# 13_RK3588_PCIE2_0_PCIE3_0.net
KiCad netlist of a schematic drawn in Altium Designer
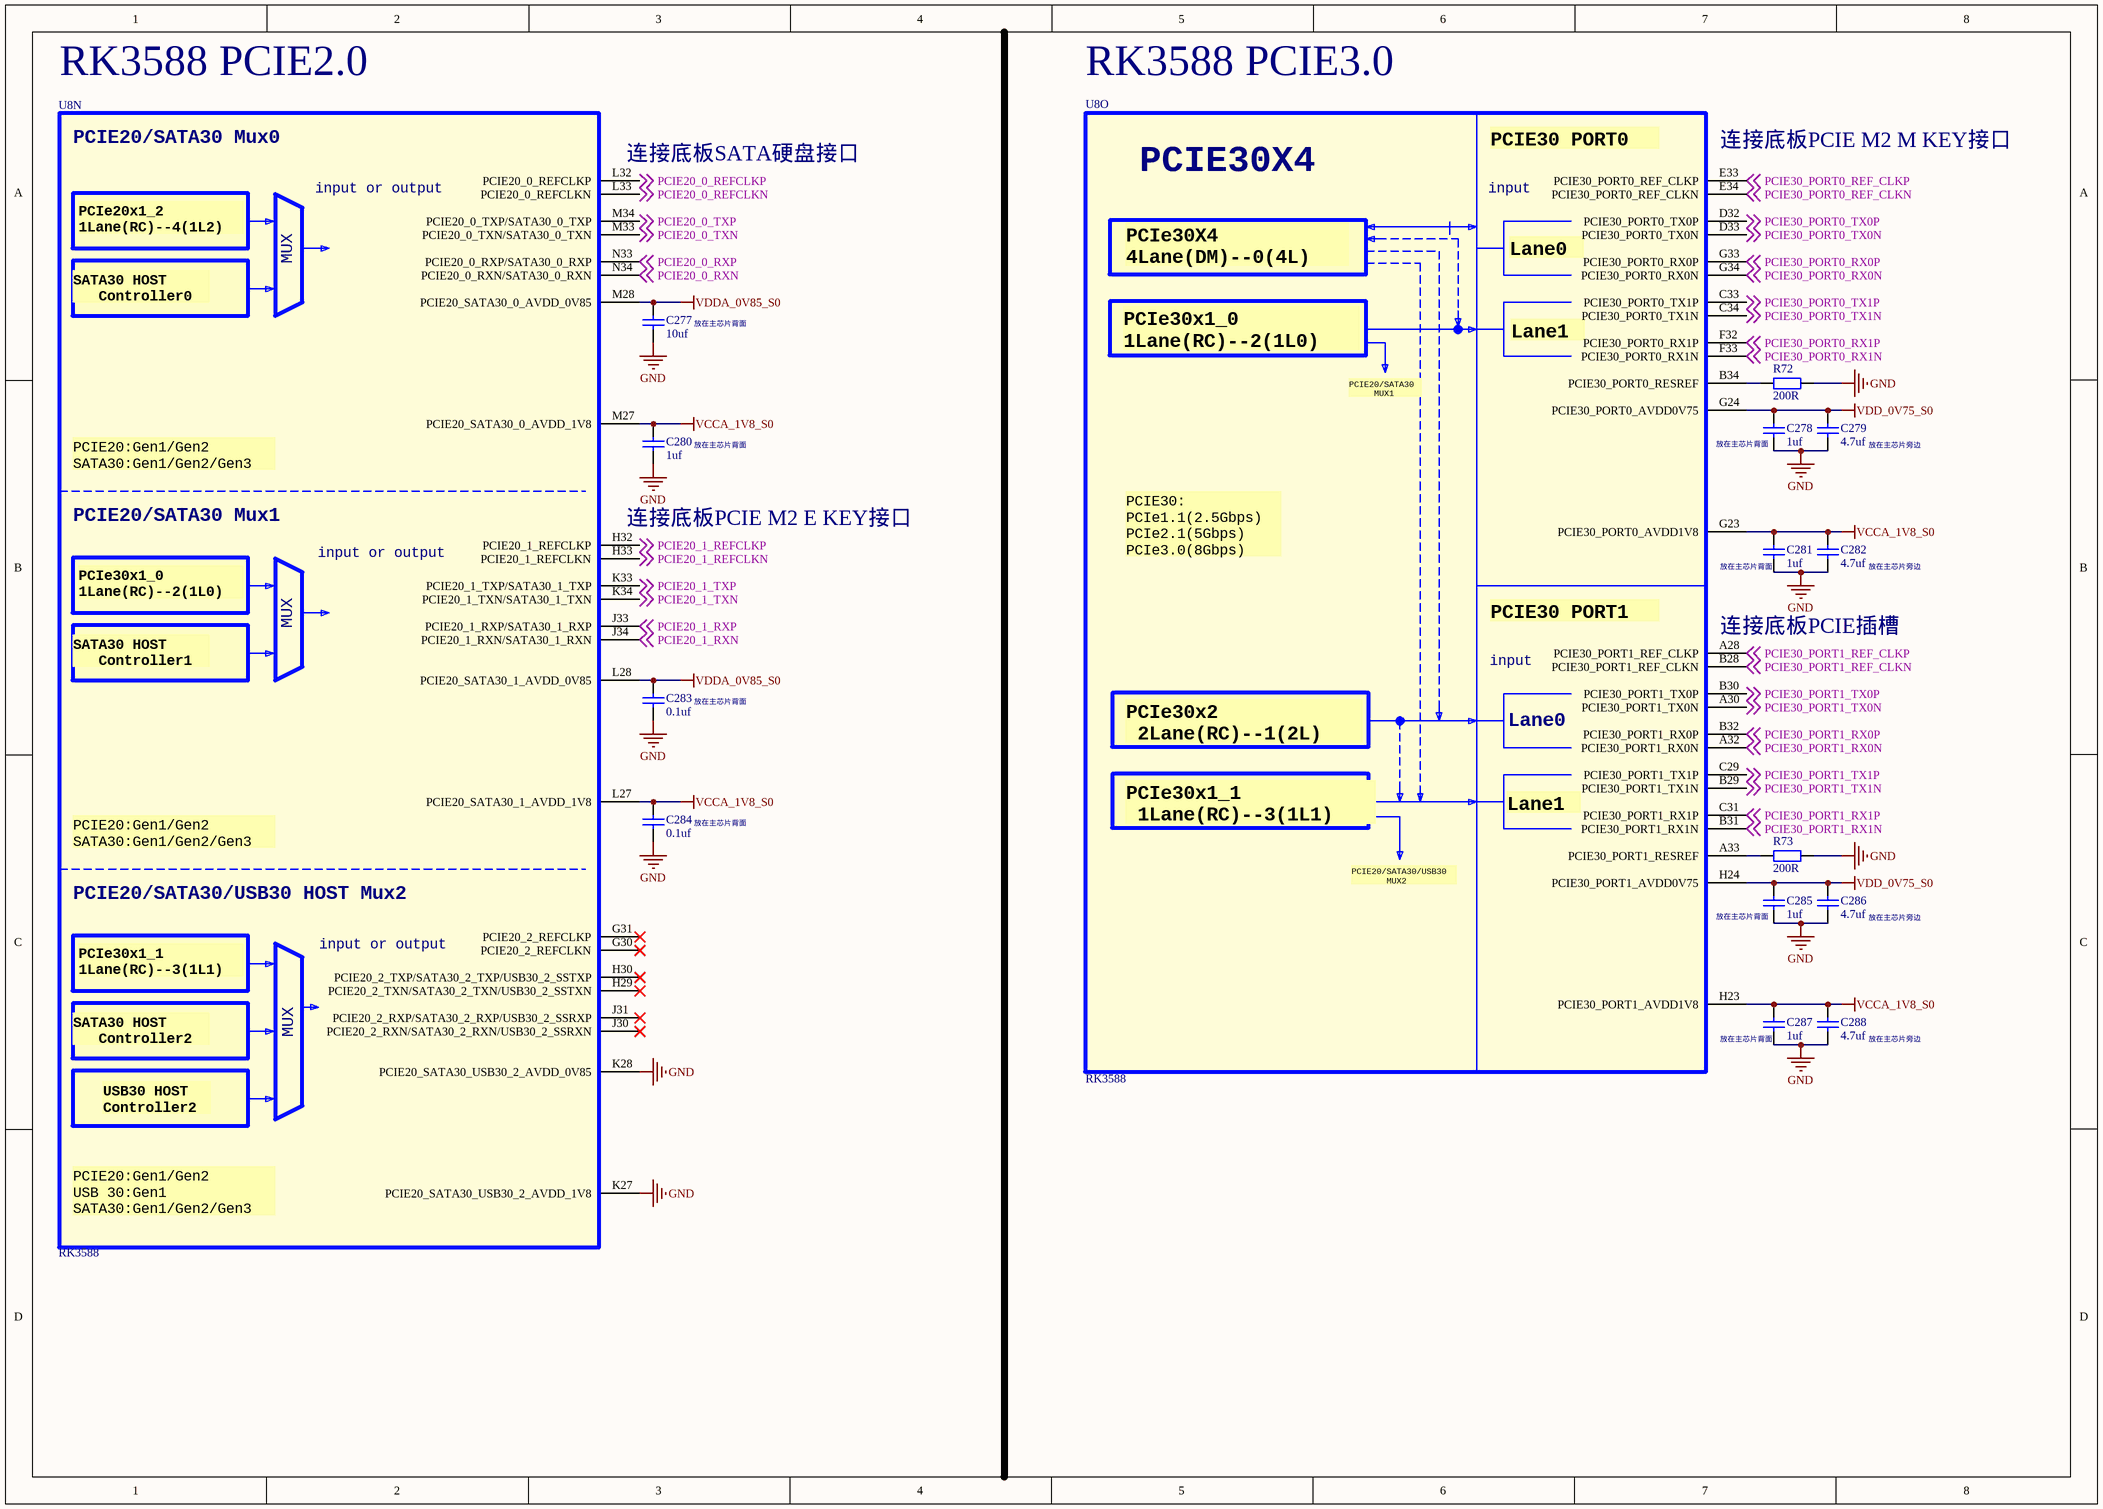
[diagram p0: 13.RK3588_PCIE2.0_PCIE3.0.SchDoc]

(export (version "E")
  (design (tool "Eeschema 10.0.6"))
  (components
    (comp (ref "C277")
      (value "10uf")
      (footprint "0.PCB1:C0201_L")
      (description "贴片电容/MLCC电容")
      (libsource (lib "RK3588") (part "C"))
    )
    (comp (ref "C278")
      (value "1uf")
      (footprint "0.PCB1:C0201_L")
      (description "贴片电容/MLCC电容")
      (libsource (lib "RK3588") (part "C"))
    )
    (comp (ref "C279")
      (value "4.7uf")
      (footprint "0.PCB1:C0402_L")
      (description "贴片电容/MLCC电容")
      (libsource (lib "RK3588") (part "C"))
    )
    (comp (ref "C280")
      (value "1uf")
      (footprint "0.PCB1:C0201_L")
      (description "贴片电容/MLCC电容")
      (libsource (lib "RK3588") (part "C"))
    )
    (comp (ref "C281")
      (value "1uf")
      (footprint "0.PCB1:C0201_L")
      (description "贴片电容/MLCC电容")
      (libsource (lib "RK3588") (part "C"))
    )
    (comp (ref "C282")
      (value "4.7uf")
      (footprint "0.PCB1:C0402_L")
      (description "贴片电容/MLCC电容")
      (libsource (lib "RK3588") (part "C"))
    )
    (comp (ref "C283")
      (value "0.1uf")
      (footprint "0.PCB1:C0201_L")
      (description "贴片电容/MLCC电容")
      (libsource (lib "RK3588") (part "C"))
    )
    (comp (ref "C284")
      (value "0.1uf")
      (footprint "0.PCB1:C0201_L")
      (description "贴片电容/MLCC电容")
      (libsource (lib "RK3588") (part "C"))
    )
    (comp (ref "C285")
      (value "1uf")
      (footprint "0.PCB1:C0201_L")
      (description "贴片电容/MLCC电容")
      (libsource (lib "RK3588") (part "C"))
    )
    (comp (ref "C286")
      (value "4.7uf")
      (footprint "0.PCB1:C0402_L")
      (description "贴片电容/MLCC电容")
      (libsource (lib "RK3588") (part "C"))
    )
    (comp (ref "C287")
      (value "1uf")
      (footprint "0.PCB1:C0201_L")
      (description "贴片电容/MLCC电容")
      (libsource (lib "RK3588") (part "C"))
    )
    (comp (ref "C288")
      (value "4.7uf")
      (footprint "0.PCB1:C0402_L")
      (description "贴片电容/MLCC电容")
      (libsource (lib "RK3588") (part "C"))
    )
    (comp (ref "R72")
      (value "200R")
      (footprint "0.PCB1:R0201_L")
      (description "贴片电阻")
      (libsource (lib "RK3588") (part "R"))
    )
    (comp (ref "R73")
      (value "200R")
      (footprint "0.PCB1:R0201_L")
      (description "贴片电阻")
      (libsource (lib "RK3588") (part "R"))
    )
    (comp (ref "U8")
      (value "RK3588")
      (footprint "0.PCB1:BGA1088_23R00X23R00X2R00")
      (description "ROCKCHIP SOC")
      (libsource (lib "RK3588") (part "SOC_RK3588"))
    )
  )
  (nets
    (net (code "1") (name "GND") (class "Default")
      (node (ref "C277") (pin "1") (pinfunction "1_1") (pintype "passive"))
      (node (ref "C278") (pin "1") (pinfunction "1_1") (pintype "passive"))
      (node (ref "C279") (pin "1") (pinfunction "1_1") (pintype "passive"))
      (node (ref "C280") (pin "1") (pinfunction "1_1") (pintype "passive"))
      (node (ref "C281") (pin "1") (pinfunction "1_1") (pintype "passive"))
      (node (ref "C282") (pin "1") (pinfunction "1_1") (pintype "passive"))
      (node (ref "C283") (pin "1") (pinfunction "1_1") (pintype "passive"))
      (node (ref "C284") (pin "1") (pinfunction "1_1") (pintype "passive"))
      (node (ref "C285") (pin "1") (pinfunction "1_1") (pintype "passive"))
      (node (ref "C286") (pin "1") (pinfunction "1_1") (pintype "passive"))
      (node (ref "C287") (pin "1") (pinfunction "1_1") (pintype "passive"))
      (node (ref "C288") (pin "1") (pinfunction "1_1") (pintype "passive"))
      (node (ref "R72") (pin "2") (pinfunction "2_2") (pintype "passive"))
      (node (ref "R73") (pin "2") (pinfunction "2_2") (pintype "passive"))
      (node (ref "U8") (pin "K27") (pinfunction "PCIE20_SATA30_USB30_2_AVDD_1V8_K27") (pintype "passive"))
      (node (ref "U8") (pin "K28") (pinfunction "PCIE20_SATA30_USB30_2_AVDD_0V85_K28") (pintype "passive"))
    )
    (net (code "2") (name "Net-(U8O-PCIE30_PORT0_RESREF)") (class "Default")
      (node (ref "R72") (pin "1") (pinfunction "1_1") (pintype "passive"))
      (node (ref "U8") (pin "B34") (pinfunction "PCIE30_PORT0_RESREF_B34") (pintype "passive"))
    )
    (net (code "3") (name "Net-(U8O-PCIE30_PORT1_RESREF)") (class "Default")
      (node (ref "R73") (pin "1") (pinfunction "1_1") (pintype "passive"))
      (node (ref "U8") (pin "A33") (pinfunction "PCIE30_PORT1_RESREF_A33") (pintype "passive"))
    )
    (net (code "4") (name "PCIE20_0_REFCLKN") (class "Default")
      (node (ref "U8") (pin "L33") (pinfunction "PCIE20_0_REFCLKN_L33") (pintype "passive"))
    )
    (net (code "5") (name "PCIE20_0_REFCLKP") (class "Default")
      (node (ref "U8") (pin "L32") (pinfunction "PCIE20_0_REFCLKP_L32") (pintype "passive"))
    )
    (net (code "6") (name "PCIE20_0_RXN") (class "Default")
      (node (ref "U8") (pin "N34") (pinfunction "PCIE20_0_RXN/SATA30_0_RXN_N34") (pintype "passive"))
    )
    (net (code "7") (name "PCIE20_0_RXP") (class "Default")
      (node (ref "U8") (pin "N33") (pinfunction "PCIE20_0_RXP/SATA30_0_RXP_N33") (pintype "passive"))
    )
    (net (code "8") (name "PCIE20_0_TXN") (class "Default")
      (node (ref "U8") (pin "M33") (pinfunction "PCIE20_0_TXN/SATA30_0_TXN_M33") (pintype "passive"))
    )
    (net (code "9") (name "PCIE20_0_TXP") (class "Default")
      (node (ref "U8") (pin "M34") (pinfunction "PCIE20_0_TXP/SATA30_0_TXP_M34") (pintype "passive"))
    )
    (net (code "10") (name "PCIE20_1_REFCLKN") (class "Default")
      (node (ref "U8") (pin "H33") (pinfunction "PCIE20_1_REFCLKN_H33") (pintype "passive"))
    )
    (net (code "11") (name "PCIE20_1_REFCLKP") (class "Default")
      (node (ref "U8") (pin "H32") (pinfunction "PCIE20_1_REFCLKP_H32") (pintype "passive"))
    )
    (net (code "12") (name "PCIE20_1_RXN") (class "Default")
      (node (ref "U8") (pin "J34") (pinfunction "PCIE20_1_RXN/SATA30_1_RXN_J34") (pintype "passive"))
    )
    (net (code "13") (name "PCIE20_1_RXP") (class "Default")
      (node (ref "U8") (pin "J33") (pinfunction "PCIE20_1_RXP/SATA30_1_RXP_J33") (pintype "passive"))
    )
    (net (code "14") (name "PCIE20_1_TXN") (class "Default")
      (node (ref "U8") (pin "K34") (pinfunction "PCIE20_1_TXN/SATA30_1_TXN_K34") (pintype "passive"))
    )
    (net (code "15") (name "PCIE20_1_TXP") (class "Default")
      (node (ref "U8") (pin "K33") (pinfunction "PCIE20_1_TXP/SATA30_1_TXP_K33") (pintype "passive"))
    )
    (net (code "16") (name "PCIE30_PORT0_REF_CLKN") (class "Default")
      (node (ref "U8") (pin "E34") (pinfunction "PCIE30_PORT0_REF_CLKN_E34") (pintype "passive"))
    )
    (net (code "17") (name "PCIE30_PORT0_REF_CLKP") (class "Default")
      (node (ref "U8") (pin "E33") (pinfunction "PCIE30_PORT0_REF_CLKP_E33") (pintype "passive"))
    )
    (net (code "18") (name "PCIE30_PORT0_RX0N") (class "Default")
      (node (ref "U8") (pin "G34") (pinfunction "PCIE30_PORT0_RX0N_G34") (pintype "passive"))
    )
    (net (code "19") (name "PCIE30_PORT0_RX0P") (class "Default")
      (node (ref "U8") (pin "G33") (pinfunction "PCIE30_PORT0_RX0P_G33") (pintype "passive"))
    )
    (net (code "20") (name "PCIE30_PORT0_RX1N") (class "Default")
      (node (ref "U8") (pin "F33") (pinfunction "PCIE30_PORT0_RX1N_F33") (pintype "passive"))
    )
    (net (code "21") (name "PCIE30_PORT0_RX1P") (class "Default")
      (node (ref "U8") (pin "F32") (pinfunction "PCIE30_PORT0_RX1P_F32") (pintype "passive"))
    )
    (net (code "22") (name "PCIE30_PORT0_TX0N") (class "Default")
      (node (ref "U8") (pin "D33") (pinfunction "PCIE30_PORT0_TX0N_D33") (pintype "passive"))
    )
    (net (code "23") (name "PCIE30_PORT0_TX0P") (class "Default")
      (node (ref "U8") (pin "D32") (pinfunction "PCIE30_PORT0_TX0P_D32") (pintype "passive"))
    )
    (net (code "24") (name "PCIE30_PORT0_TX1N") (class "Default")
      (node (ref "U8") (pin "C34") (pinfunction "PCIE30_PORT0_TX1N_C34") (pintype "passive"))
    )
    (net (code "25") (name "PCIE30_PORT0_TX1P") (class "Default")
      (node (ref "U8") (pin "C33") (pinfunction "PCIE30_PORT0_TX1P_C33") (pintype "passive"))
    )
    (net (code "26") (name "PCIE30_PORT1_REF_CLKN") (class "Default")
      (node (ref "U8") (pin "B28") (pinfunction "PCIE30_PORT1_REF_CLKN_B28") (pintype "passive"))
    )
    (net (code "27") (name "PCIE30_PORT1_REF_CLKP") (class "Default")
      (node (ref "U8") (pin "A28") (pinfunction "PCIE30_PORT1_REF_CLKP_A28") (pintype "passive"))
    )
    (net (code "28") (name "PCIE30_PORT1_RX0N") (class "Default")
      (node (ref "U8") (pin "A32") (pinfunction "PCIE30_PORT1_RX0N_A32") (pintype "passive"))
    )
    (net (code "29") (name "PCIE30_PORT1_RX0P") (class "Default")
      (node (ref "U8") (pin "B32") (pinfunction "PCIE30_PORT1_RX0P_B32") (pintype "passive"))
    )
    (net (code "30") (name "PCIE30_PORT1_RX1N") (class "Default")
      (node (ref "U8") (pin "B31") (pinfunction "PCIE30_PORT1_RX1N_B31") (pintype "passive"))
    )
    (net (code "31") (name "PCIE30_PORT1_RX1P") (class "Default")
      (node (ref "U8") (pin "C31") (pinfunction "PCIE30_PORT1_RX1P_C31") (pintype "passive"))
    )
    (net (code "32") (name "PCIE30_PORT1_TX0N") (class "Default")
      (node (ref "U8") (pin "A30") (pinfunction "PCIE30_PORT1_TX0N_A30") (pintype "passive"))
    )
    (net (code "33") (name "PCIE30_PORT1_TX0P") (class "Default")
      (node (ref "U8") (pin "B30") (pinfunction "PCIE30_PORT1_TX0P_B30") (pintype "passive"))
    )
    (net (code "34") (name "PCIE30_PORT1_TX1N") (class "Default")
      (node (ref "U8") (pin "B29") (pinfunction "PCIE30_PORT1_TX1N_B29") (pintype "passive"))
    )
    (net (code "35") (name "PCIE30_PORT1_TX1P") (class "Default")
      (node (ref "U8") (pin "C29") (pinfunction "PCIE30_PORT1_TX1P_C29") (pintype "passive"))
    )
    (net (code "36") (name "VCCA_1V8_S0") (class "Default")
      (node (ref "C280") (pin "2") (pinfunction "2_2") (pintype "passive"))
      (node (ref "C281") (pin "2") (pinfunction "2_2") (pintype "passive"))
      (node (ref "C282") (pin "2") (pinfunction "2_2") (pintype "passive"))
      (node (ref "C284") (pin "2") (pinfunction "2_2") (pintype "passive"))
      (node (ref "C287") (pin "2") (pinfunction "2_2") (pintype "passive"))
      (node (ref "C288") (pin "2") (pinfunction "2_2") (pintype "passive"))
      (node (ref "U8") (pin "G23") (pinfunction "PCIE30_PORT0_AVDD1V8_G23") (pintype "passive"))
      (node (ref "U8") (pin "H23") (pinfunction "PCIE30_PORT1_AVDD1V8_H23") (pintype "passive"))
      (node (ref "U8") (pin "L27") (pinfunction "PCIE20_SATA30_1_AVDD_1V8_L27") (pintype "passive"))
      (node (ref "U8") (pin "M27") (pinfunction "PCIE20_SATA30_0_AVDD_1V8_M27") (pintype "passive"))
    )
    (net (code "37") (name "VDDA_0V85_S0") (class "Default")
      (node (ref "C277") (pin "2") (pinfunction "2_2") (pintype "passive"))
      (node (ref "C283") (pin "2") (pinfunction "2_2") (pintype "passive"))
      (node (ref "U8") (pin "L28") (pinfunction "PCIE20_SATA30_1_AVDD_0V85_L28") (pintype "passive"))
      (node (ref "U8") (pin "M28") (pinfunction "PCIE20_SATA30_0_AVDD_0V85_M28") (pintype "passive"))
    )
    (net (code "38") (name "VDD_0V75_S0") (class "Default")
      (node (ref "C278") (pin "2") (pinfunction "2_2") (pintype "passive"))
      (node (ref "C279") (pin "2") (pinfunction "2_2") (pintype "passive"))
      (node (ref "C285") (pin "2") (pinfunction "2_2") (pintype "passive"))
      (node (ref "C286") (pin "2") (pinfunction "2_2") (pintype "passive"))
      (node (ref "U8") (pin "G24") (pinfunction "PCIE30_PORT0_AVDD0V75_G24") (pintype "passive"))
      (node (ref "U8") (pin "H24") (pinfunction "PCIE30_PORT1_AVDD0V75_H24") (pintype "passive"))
    )
    (net (code "39") (name "unconnected-(U8N-PCIE20_2_REFCLKN-PadG30)") (class "Default")
      (node (ref "U8") (pin "G30") (pinfunction "PCIE20_2_REFCLKN_G30") (pintype "passive+no_connect"))
    )
    (net (code "40") (name "unconnected-(U8N-PCIE20_2_REFCLKP-PadG31)") (class "Default")
      (node (ref "U8") (pin "G31") (pinfunction "PCIE20_2_REFCLKP_G31") (pintype "passive+no_connect"))
    )
    (net (code "41") (name "unconnected-(U8N-PCIE20_2_RXN{slash}SATA30_2_RXN{slash}USB30_2_SSRXN-PadJ30)") (class "Default")
      (node (ref "U8") (pin "J30") (pinfunction "PCIE20_2_RXN/SATA30_2_RXN/USB30_2_SSRXN_J30") (pintype "passive+no_connect"))
    )
    (net (code "42") (name "unconnected-(U8N-PCIE20_2_RXP{slash}SATA30_2_RXP{slash}USB30_2_SSRXP-PadJ31)") (class "Default")
      (node (ref "U8") (pin "J31") (pinfunction "PCIE20_2_RXP/SATA30_2_RXP/USB30_2_SSRXP_J31") (pintype "passive+no_connect"))
    )
    (net (code "43") (name "unconnected-(U8N-PCIE20_2_TXN{slash}SATA30_2_TXN{slash}USB30_2_SSTXN-PadH29)") (class "Default")
      (node (ref "U8") (pin "H29") (pinfunction "PCIE20_2_TXN/SATA30_2_TXN/USB30_2_SSTXN_H29") (pintype "passive+no_connect"))
    )
    (net (code "44") (name "unconnected-(U8N-PCIE20_2_TXP{slash}SATA30_2_TXP{slash}USB30_2_SSTXP-PadH30)") (class "Default")
      (node (ref "U8") (pin "H30") (pinfunction "PCIE20_2_TXP/SATA30_2_TXP/USB30_2_SSTXP_H30") (pintype "passive+no_connect"))
    )
  )
)
